# source_eagle.net
KiCad netlist of a schematic drawn in EAGLE
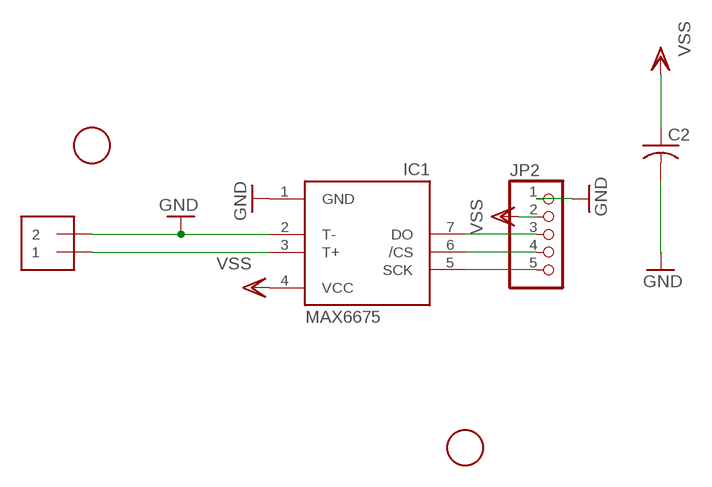
[diagram p0: schematic, sheet 1]

(export (version "E")
  (design (tool "Eeschema 10.0.6"))
  (components
    (comp (ref "C2")
      (value "C-USC0805K")
      (footprint "eagle-import:C0805K")
      (libsource (lib "eagle-import") (part "C-USC0805K"))
    )
    (comp (ref "IC1")
      (value "MAX6675")
      (footprint "eagle-import:SO08")
      (libsource (lib "eagle-import") (part "MAX6675"))
    )
    (comp (ref "J1")
      (value "1X2-3.5MM")
      (footprint "eagle-import:3.5MMTERM")
      (libsource (lib "eagle-import") (part "1X2-3.5MM"))
    )
    (comp (ref "JP2")
      (value "PINHD-1X5")
      (footprint "eagle-import:1X05")
      (libsource (lib "eagle-import") (part "PINHD-1X5"))
    )
    (comp (ref "U$1")
      (value "FIDUCIAL")
      (footprint "eagle-import:FIDUCIAL_1MM")
      (libsource (lib "eagle-import") (part "FIDUCIAL"))
    )
    (comp (ref "U$2")
      (value "FIDUCIAL")
      (footprint "eagle-import:FIDUCIAL_1MM")
      (libsource (lib "eagle-import") (part "FIDUCIAL"))
    )
  )
  (nets
    (net (code "1") (name "GND") (class "Default")
      (node (ref "C2") (pin "2") (pinfunction "2_2") (pintype "passive"))
      (node (ref "IC1") (pin "1") (pinfunction "GND_1") (pintype "power_in"))
      (node (ref "IC1") (pin "2") (pinfunction "T-_2") (pintype "input"))
      (node (ref "J1") (pin "2") (pinfunction "2_2") (pintype "passive"))
      (node (ref "JP2") (pin "1") (pinfunction "1_1") (pintype "passive"))
    )
    (net (code "2") (name "Net-(IC1-DO)") (class "Default")
      (node (ref "IC1") (pin "7") (pinfunction "DO_7") (pintype "output"))
      (node (ref "JP2") (pin "3") (pinfunction "3_3") (pintype "passive"))
    )
    (net (code "3") (name "Net-(IC1-SCK)") (class "Default")
      (node (ref "IC1") (pin "5") (pinfunction "SCK_5") (pintype "input"))
      (node (ref "JP2") (pin "5") (pinfunction "5_5") (pintype "passive"))
    )
    (net (code "4") (name "Net-(IC1-T+)") (class "Default")
      (node (ref "IC1") (pin "3") (pinfunction "T+_3") (pintype "input"))
      (node (ref "J1") (pin "1") (pinfunction "1_1") (pintype "passive"))
    )
    (net (code "5") (name "Net-(IC1-{slash}CS)") (class "Default")
      (node (ref "IC1") (pin "6") (pinfunction "/CS_6") (pintype "input"))
      (node (ref "JP2") (pin "4") (pinfunction "4_4") (pintype "passive"))
    )
    (net (code "6") (name "VSS") (class "Default")
      (node (ref "C2") (pin "1") (pinfunction "1_1") (pintype "passive"))
      (node (ref "IC1") (pin "4") (pinfunction "VCC_4") (pintype "power_in"))
      (node (ref "JP2") (pin "2") (pinfunction "2_2") (pintype "passive"))
    )
  )
)
